# tic_tac_toe.net
KiCad netlist of a schematic drawn in EAGLE
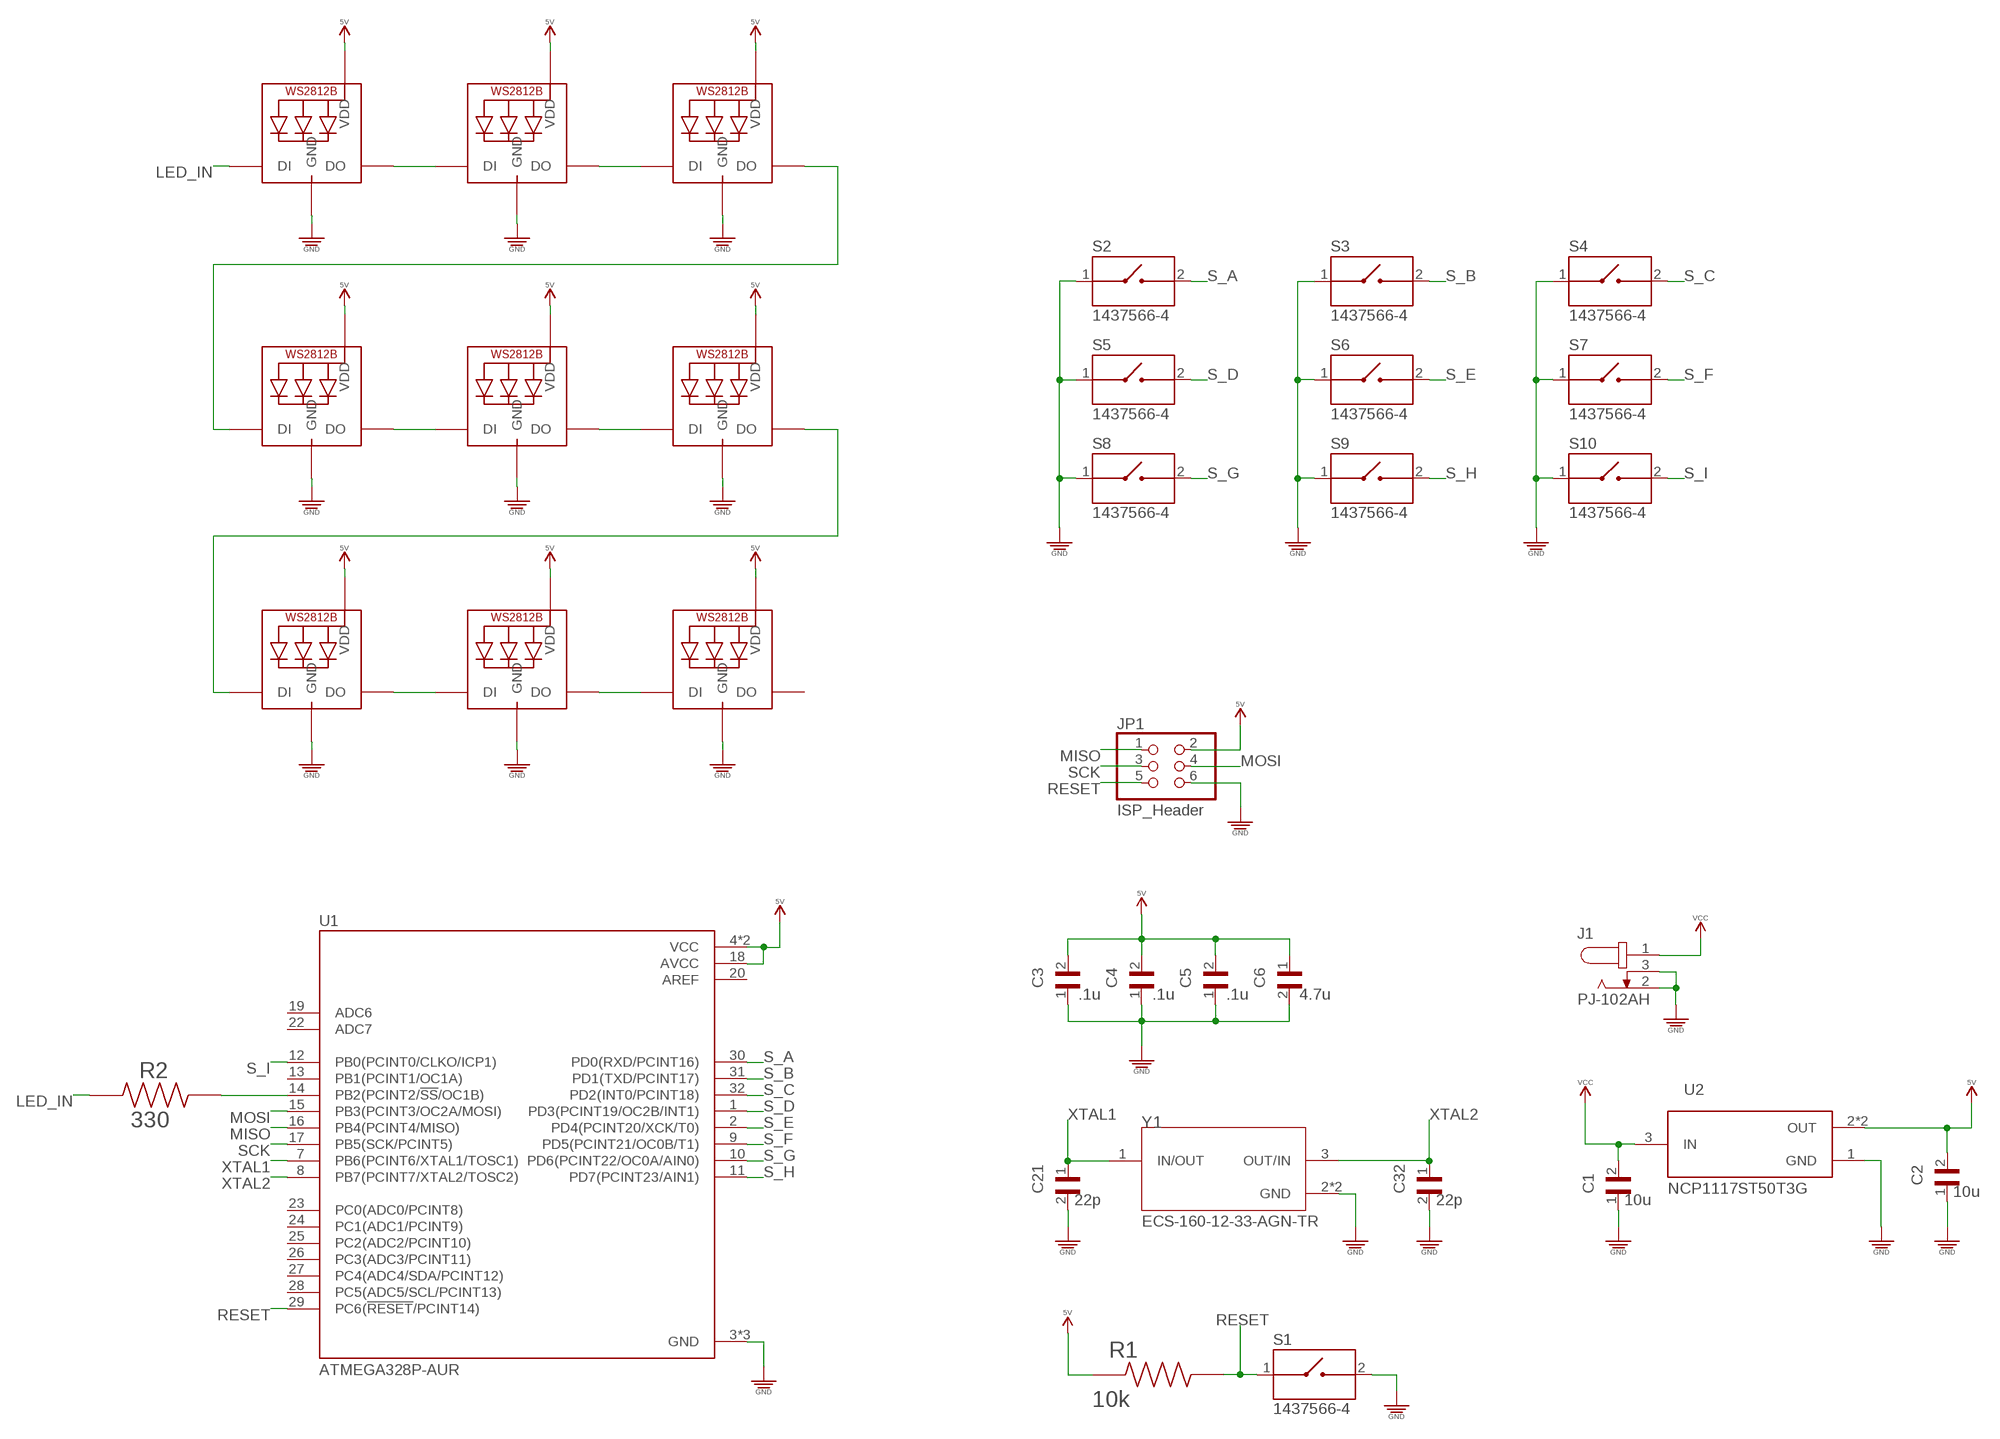
[diagram p0: schematic, sheet 1]

(export (version "E")
  (design (tool "Eeschema 10.0.6"))
  (components
    (comp (ref "C1")
      (value "10u")
      (footprint "eagle-import:CAPC2012X140N")
      (fields
        (field (name "DIGI-KEY_PART_NUMBER") "478-3051-1-ND")
        (field (name "MF") "AVX")
        (field (name "MP") "TAJR106M006R")
      )
      (libsource (lib "eagle-import") (part "TAJR106M006R"))
    )
    (comp (ref "C2")
      (value "10u")
      (footprint "eagle-import:CAPC2012X140N")
      (fields
        (field (name "DIGI-KEY_PART_NUMBER") "478-3051-1-ND")
        (field (name "MF") "AVX")
        (field (name "MP") "TAJR106M006R")
      )
      (libsource (lib "eagle-import") (part "TAJR106M006R"))
    )
    (comp (ref "C3")
      (value ".1u")
      (footprint "eagle-import:CAPC2012X140N")
      (fields
        (field (name "DIGI-KEY_PART_NUMBER") "478-3614-1-ND")
        (field (name "MF") "AVX")
        (field (name "MP") "08055F104K4T2A")
      )
      (libsource (lib "eagle-import") (part "08055F104K4T2A"))
    )
    (comp (ref "C4")
      (value ".1u")
      (footprint "eagle-import:CAPC2012X140N")
      (fields
        (field (name "DIGI-KEY_PART_NUMBER") "478-3614-1-ND")
        (field (name "MF") "AVX")
        (field (name "MP") "08055F104K4T2A")
      )
      (libsource (lib "eagle-import") (part "08055F104K4T2A"))
    )
    (comp (ref "C5")
      (value ".1u")
      (footprint "eagle-import:CAPC2012X140N")
      (fields
        (field (name "DIGI-KEY_PART_NUMBER") "478-3614-1-ND")
        (field (name "MF") "AVX")
        (field (name "MP") "08055F104K4T2A")
      )
      (libsource (lib "eagle-import") (part "08055F104K4T2A"))
    )
    (comp (ref "C6")
      (value "4.7u")
      (footprint "eagle-import:CAPC2012X140N")
      (fields
        (field (name "DIGI-KEY_PART_NUMBER") "1276-1244-1-ND")
        (field (name "MF") "Samsung Electro-Mechanics")
        (field (name "MP") "CL21A475KAQNNNE")
      )
      (libsource (lib "eagle-import") (part "CL21A475KAQNNNE"))
    )
    (comp (ref "C21")
      (value "22p")
      (footprint "eagle-import:CAPC2012X140N")
      (fields
        (field (name "DIGI-KEY_PART_NUMBER") "399-C0805C220J5GAC7800CT-ND")
        (field (name "MF") "KEMET")
        (field (name "MP") "C0805C220J5GACTU")
      )
      (libsource (lib "eagle-import") (part "C0805C220J5GACTU"))
    )
    (comp (ref "C32")
      (value "22p")
      (footprint "eagle-import:CAPC2012X140N")
      (fields
        (field (name "DIGI-KEY_PART_NUMBER") "399-C0805C220J5GAC7800CT-ND")
        (field (name "MF") "KEMET")
        (field (name "MP") "C0805C220J5GACTU")
      )
      (libsource (lib "eagle-import") (part "C0805C220J5GACTU"))
    )
    (comp (ref "J1")
      (value "PJ-102AH")
      (footprint "eagle-import:CUI_PJ-102AH")
      (fields (field (name "MF") "CUI Devices"))
      (libsource (lib "eagle-import") (part "PJ-102AH"))
    )
    (comp (ref "JP1")
      (value "ISP_Header")
      (footprint "eagle-import:2X03")
      (libsource (lib "eagle-import") (part "PINHD-2X3"))
    )
    (comp (ref "LED1")
      (value "MICROBUILDER_WS2812B_SK6812E")
      (footprint "eagle-import:MICROBUILDER_NEO3535_REVERSE")
      (libsource (lib "eagle-import") (part "MICROBUILDER_WS2812B_SK6812E"))
    )
    (comp (ref "LED2")
      (value "MICROBUILDER_WS2812B_SK6812E")
      (footprint "eagle-import:MICROBUILDER_NEO3535_REVERSE")
      (libsource (lib "eagle-import") (part "MICROBUILDER_WS2812B_SK6812E"))
    )
    (comp (ref "LED3")
      (value "MICROBUILDER_WS2812B_SK6812E")
      (footprint "eagle-import:MICROBUILDER_NEO3535_REVERSE")
      (libsource (lib "eagle-import") (part "MICROBUILDER_WS2812B_SK6812E"))
    )
    (comp (ref "LED4")
      (value "MICROBUILDER_WS2812B_SK6812E")
      (footprint "eagle-import:MICROBUILDER_NEO3535_REVERSE")
      (libsource (lib "eagle-import") (part "MICROBUILDER_WS2812B_SK6812E"))
    )
    (comp (ref "LED5")
      (value "MICROBUILDER_WS2812B_SK6812E")
      (footprint "eagle-import:MICROBUILDER_NEO3535_REVERSE")
      (libsource (lib "eagle-import") (part "MICROBUILDER_WS2812B_SK6812E"))
    )
    (comp (ref "LED6")
      (value "MICROBUILDER_WS2812B_SK6812E")
      (footprint "eagle-import:MICROBUILDER_NEO3535_REVERSE")
      (libsource (lib "eagle-import") (part "MICROBUILDER_WS2812B_SK6812E"))
    )
    (comp (ref "LED7")
      (value "MICROBUILDER_WS2812B_SK6812E")
      (footprint "eagle-import:MICROBUILDER_NEO3535_REVERSE")
      (libsource (lib "eagle-import") (part "MICROBUILDER_WS2812B_SK6812E"))
    )
    (comp (ref "LED8")
      (value "MICROBUILDER_WS2812B_SK6812E")
      (footprint "eagle-import:MICROBUILDER_NEO3535_REVERSE")
      (libsource (lib "eagle-import") (part "MICROBUILDER_WS2812B_SK6812E"))
    )
    (comp (ref "LED9")
      (value "MICROBUILDER_WS2812B_SK6812E")
      (footprint "eagle-import:MICROBUILDER_NEO3535_REVERSE")
      (libsource (lib "eagle-import") (part "MICROBUILDER_WS2812B_SK6812E"))
    )
    (comp (ref "R1")
      (value "10k")
      (footprint "eagle-import:RESC2012X60N")
      (fields
        (field (name "DIGI-KEY_PART_NUMBER") "CR0805-FX-1002ELFTR-ND")
        (field (name "MF") "Bourns")
        (field (name "MP") "CR0805-FX-1002ELF")
      )
      (libsource (lib "eagle-import") (part "CR0805-FX-1002ELF"))
    )
    (comp (ref "R2")
      (value "330")
      (footprint "eagle-import:RESC3116X65N")
      (fields
        (field (name "DIGI-KEY_PART_NUMBER") "311-330FRCT-ND")
        (field (name "MF") "Yageo")
        (field (name "MP") "RC1206FR-07330RL")
      )
      (libsource (lib "eagle-import") (part "RC1206FR-07330RL"))
    )
    (comp (ref "S1")
      (value "1437566-4")
      (footprint "eagle-import:SW_1437566-4")
      (fields
        (field (name "DIGI-KEY_PART_NUMBER") "2266-1437566-4TR-ND")
        (field (name "MF") "TE Connectivity")
      )
      (libsource (lib "eagle-import") (part "1437566-4"))
    )
    (comp (ref "S2")
      (value "1437566-4")
      (footprint "eagle-import:SW_1437566-4")
      (fields
        (field (name "DIGI-KEY_PART_NUMBER") "2266-1437566-4TR-ND")
        (field (name "MF") "TE Connectivity")
      )
      (libsource (lib "eagle-import") (part "1437566-4"))
    )
    (comp (ref "S3")
      (value "1437566-4")
      (footprint "eagle-import:SW_1437566-4")
      (fields
        (field (name "DIGI-KEY_PART_NUMBER") "2266-1437566-4TR-ND")
        (field (name "MF") "TE Connectivity")
      )
      (libsource (lib "eagle-import") (part "1437566-4"))
    )
    (comp (ref "S4")
      (value "1437566-4")
      (footprint "eagle-import:SW_1437566-4")
      (fields
        (field (name "DIGI-KEY_PART_NUMBER") "2266-1437566-4TR-ND")
        (field (name "MF") "TE Connectivity")
      )
      (libsource (lib "eagle-import") (part "1437566-4"))
    )
    (comp (ref "S5")
      (value "1437566-4")
      (footprint "eagle-import:SW_1437566-4")
      (fields
        (field (name "DIGI-KEY_PART_NUMBER") "2266-1437566-4TR-ND")
        (field (name "MF") "TE Connectivity")
      )
      (libsource (lib "eagle-import") (part "1437566-4"))
    )
    (comp (ref "S6")
      (value "1437566-4")
      (footprint "eagle-import:SW_1437566-4")
      (fields
        (field (name "DIGI-KEY_PART_NUMBER") "2266-1437566-4TR-ND")
        (field (name "MF") "TE Connectivity")
      )
      (libsource (lib "eagle-import") (part "1437566-4"))
    )
    (comp (ref "S7")
      (value "1437566-4")
      (footprint "eagle-import:SW_1437566-4")
      (fields
        (field (name "DIGI-KEY_PART_NUMBER") "2266-1437566-4TR-ND")
        (field (name "MF") "TE Connectivity")
      )
      (libsource (lib "eagle-import") (part "1437566-4"))
    )
    (comp (ref "S8")
      (value "1437566-4")
      (footprint "eagle-import:SW_1437566-4")
      (fields
        (field (name "DIGI-KEY_PART_NUMBER") "2266-1437566-4TR-ND")
        (field (name "MF") "TE Connectivity")
      )
      (libsource (lib "eagle-import") (part "1437566-4"))
    )
    (comp (ref "S9")
      (value "1437566-4")
      (footprint "eagle-import:SW_1437566-4")
      (fields
        (field (name "DIGI-KEY_PART_NUMBER") "2266-1437566-4TR-ND")
        (field (name "MF") "TE Connectivity")
      )
      (libsource (lib "eagle-import") (part "1437566-4"))
    )
    (comp (ref "S10")
      (value "1437566-4")
      (footprint "eagle-import:SW_1437566-4")
      (fields
        (field (name "DIGI-KEY_PART_NUMBER") "2266-1437566-4TR-ND")
        (field (name "MF") "TE Connectivity")
      )
      (libsource (lib "eagle-import") (part "1437566-4"))
    )
    (comp (ref "U1")
      (value "ATMEGA328P-AUR")
      (footprint "eagle-import:QFP80P900X900X120-32N")
      (fields
        (field (name "DIGI-KEY_PART_NUMBER") "ATMEGA328P-AURTR-ND")
        (field (name "MF") "Microchip Technology")
      )
      (libsource (lib "eagle-import") (part "ATMEGA328P-AUR"))
    )
    (comp (ref "U2")
      (value "NCP1117ST50T3G")
      (footprint "eagle-import:SOT230P700X180-4N")
      (fields
        (field (name "DIGI-KEY_PART_NUMBER") "NCP1117ST50T3GOSCT-ND")
        (field (name "MF") "ON Semiconductor")
      )
      (libsource (lib "eagle-import") (part "NCP1117ST50T3G"))
    )
    (comp (ref "Y1")
      (value "ECS-160-12-33-AGN-TR")
      (footprint "eagle-import:XTAL_ECS-160-12-33-AGN-TR")
      (fields (field (name "DIGI-KEY_PART_NUMBER") "XC2930CT-ND") (field (name "MF") "ECS Inc."))
      (libsource (lib "eagle-import") (part "ECS-160-12-33-AGN-TR"))
    )
  )
  (nets
    (net (code "1") (name "/AREF") (class "Default")
      (node (ref "U1") (pin "20") (pinfunction "AREF_20") (pintype "power_in"))
    )
    (net (code "2") (name "/LED_IN") (class "Default")
      (node (ref "LED1") (pin "4-DIN") (pinfunction "DI_4-DIN") (pintype "input"))
      (node (ref "R2") (pin "1") (pinfunction "1_1") (pintype "passive"))
    )
    (net (code "3") (name "/MISO") (class "Default")
      (node (ref "JP1") (pin "1") (pinfunction "1_1") (pintype "passive"))
      (node (ref "U1") (pin "16") (pinfunction "PB4(PCINT4/MISO)_16") (pintype "bidirectional"))
    )
    (net (code "4") (name "/MOSI") (class "Default")
      (node (ref "JP1") (pin "4") (pinfunction "4_4") (pintype "passive"))
      (node (ref "U1") (pin "15") (pinfunction "PB3(PCINT3/OC2A/MOSI)_15") (pintype "bidirectional"))
    )
    (net (code "5") (name "/RESET") (class "Default")
      (node (ref "JP1") (pin "5") (pinfunction "5_5") (pintype "passive"))
      (node (ref "R1") (pin "2") (pinfunction "2_2") (pintype "passive"))
      (node (ref "S1") (pin "1") (pinfunction "1_1") (pintype "passive"))
      (node (ref "U1") (pin "29") (pinfunction "PC6(~{RESET}/PCINT14)_29") (pintype "bidirectional"))
    )
    (net (code "6") (name "/SCK") (class "Default")
      (node (ref "JP1") (pin "3") (pinfunction "3_3") (pintype "passive"))
      (node (ref "U1") (pin "17") (pinfunction "PB5(SCK/PCINT5)_17") (pintype "bidirectional"))
    )
    (net (code "7") (name "/S_A") (class "Default")
      (node (ref "S2") (pin "2") (pinfunction "2_2") (pintype "passive"))
      (node (ref "U1") (pin "30") (pinfunction "PD0(RXD/PCINT16)_30") (pintype "bidirectional"))
    )
    (net (code "8") (name "/S_B") (class "Default")
      (node (ref "S3") (pin "2") (pinfunction "2_2") (pintype "passive"))
      (node (ref "U1") (pin "31") (pinfunction "PD1(TXD/PCINT17)_31") (pintype "bidirectional"))
    )
    (net (code "9") (name "/S_C") (class "Default")
      (node (ref "S4") (pin "2") (pinfunction "2_2") (pintype "passive"))
      (node (ref "U1") (pin "32") (pinfunction "PD2(INT0/PCINT18)_32") (pintype "bidirectional"))
    )
    (net (code "10") (name "/S_D") (class "Default")
      (node (ref "S5") (pin "2") (pinfunction "2_2") (pintype "passive"))
      (node (ref "U1") (pin "1") (pinfunction "PD3(PCINT19/OC2B/INT1)_1") (pintype "bidirectional"))
    )
    (net (code "11") (name "/S_E") (class "Default")
      (node (ref "S6") (pin "2") (pinfunction "2_2") (pintype "passive"))
      (node (ref "U1") (pin "2") (pinfunction "PD4(PCINT20/XCK/T0)_2") (pintype "bidirectional"))
    )
    (net (code "12") (name "/S_F") (class "Default")
      (node (ref "S7") (pin "2") (pinfunction "2_2") (pintype "passive"))
      (node (ref "U1") (pin "9") (pinfunction "PD5(PCINT21/OC0B/T1)_9") (pintype "bidirectional"))
    )
    (net (code "13") (name "/S_G") (class "Default")
      (node (ref "S8") (pin "2") (pinfunction "2_2") (pintype "passive"))
      (node (ref "U1") (pin "10") (pinfunction "PD6(PCINT22/OC0A/AIN0)_10") (pintype "bidirectional"))
    )
    (net (code "14") (name "/S_H") (class "Default")
      (node (ref "S9") (pin "2") (pinfunction "2_2") (pintype "passive"))
      (node (ref "U1") (pin "11") (pinfunction "PD7(PCINT23/AIN1)_11") (pintype "bidirectional"))
    )
    (net (code "15") (name "/S_I") (class "Default")
      (node (ref "S10") (pin "2") (pinfunction "2_2") (pintype "passive"))
      (node (ref "U1") (pin "12") (pinfunction "PB0(PCINT0/CLKO/ICP1)_12") (pintype "bidirectional"))
    )
    (net (code "16") (name "/XTAL1") (class "Default")
      (node (ref "C21") (pin "1") (pinfunction "1_1") (pintype "passive"))
      (node (ref "U1") (pin "7") (pinfunction "PB6(PCINT6/XTAL1/TOSC1)_7") (pintype "bidirectional"))
      (node (ref "Y1") (pin "1") (pinfunction "IN/OUT_1") (pintype "bidirectional"))
    )
    (net (code "17") (name "/XTAL2") (class "Default")
      (node (ref "C32") (pin "1") (pinfunction "1_1") (pintype "passive"))
      (node (ref "U1") (pin "8") (pinfunction "PB7(PCINT7/XTAL2/TOSC2)_8") (pintype "bidirectional"))
      (node (ref "Y1") (pin "3") (pinfunction "OUT/IN_3") (pintype "bidirectional"))
    )
    (net (code "18") (name "5V") (class "Default")
      (node (ref "C2") (pin "2") (pinfunction "2_2") (pintype "passive"))
      (node (ref "C3") (pin "2") (pinfunction "2_2") (pintype "passive"))
      (node (ref "C4") (pin "2") (pinfunction "2_2") (pintype "passive"))
      (node (ref "C5") (pin "2") (pinfunction "2_2") (pintype "passive"))
      (node (ref "C6") (pin "1") (pinfunction "1_1") (pintype "passive"))
      (node (ref "JP1") (pin "2") (pinfunction "2_2") (pintype "passive"))
      (node (ref "LED1") (pin "1-VDD") (pinfunction "VDD_1-VDD") (pintype "power_in"))
      (node (ref "LED2") (pin "1-VDD") (pinfunction "VDD_1-VDD") (pintype "power_in"))
      (node (ref "LED3") (pin "1-VDD") (pinfunction "VDD_1-VDD") (pintype "power_in"))
      (node (ref "LED4") (pin "1-VDD") (pinfunction "VDD_1-VDD") (pintype "power_in"))
      (node (ref "LED5") (pin "1-VDD") (pinfunction "VDD_1-VDD") (pintype "power_in"))
      (node (ref "LED6") (pin "1-VDD") (pinfunction "VDD_1-VDD") (pintype "power_in"))
      (node (ref "LED7") (pin "1-VDD") (pinfunction "VDD_1-VDD") (pintype "power_in"))
      (node (ref "LED8") (pin "1-VDD") (pinfunction "VDD_1-VDD") (pintype "power_in"))
      (node (ref "LED9") (pin "1-VDD") (pinfunction "VDD_1-VDD") (pintype "power_in"))
      (node (ref "R1") (pin "1") (pinfunction "1_1") (pintype "passive"))
      (node (ref "U1") (pin "18") (pinfunction "AVCC_18") (pintype "power_in"))
      (node (ref "U1") (pin "4") (pinfunction "VCC_4") (pintype "power_in"))
      (node (ref "U1") (pin "6") (pinfunction "VCC_6") (pintype "power_in"))
      (node (ref "U2") (pin "2") (pinfunction "OUT_2") (pintype "output"))
      (node (ref "U2") (pin "4") (pinfunction "OUT_4") (pintype "output"))
    )
    (net (code "19") (name "GND") (class "Default")
      (node (ref "C1") (pin "1") (pinfunction "1_1") (pintype "passive"))
      (node (ref "C2") (pin "1") (pinfunction "1_1") (pintype "passive"))
      (node (ref "C21") (pin "2") (pinfunction "2_2") (pintype "passive"))
      (node (ref "C3") (pin "1") (pinfunction "1_1") (pintype "passive"))
      (node (ref "C32") (pin "2") (pinfunction "2_2") (pintype "passive"))
      (node (ref "C4") (pin "1") (pinfunction "1_1") (pintype "passive"))
      (node (ref "C5") (pin "1") (pinfunction "1_1") (pintype "passive"))
      (node (ref "C6") (pin "2") (pinfunction "2_2") (pintype "passive"))
      (node (ref "J1") (pin "2") (pinfunction "2_2") (pintype "passive"))
      (node (ref "J1") (pin "3") (pinfunction "3_3") (pintype "passive"))
      (node (ref "JP1") (pin "6") (pinfunction "6_6") (pintype "passive"))
      (node (ref "LED1") (pin "3-GND") (pinfunction "GND_3-GND") (pintype "power_in"))
      (node (ref "LED2") (pin "3-GND") (pinfunction "GND_3-GND") (pintype "power_in"))
      (node (ref "LED3") (pin "3-GND") (pinfunction "GND_3-GND") (pintype "power_in"))
      (node (ref "LED4") (pin "3-GND") (pinfunction "GND_3-GND") (pintype "power_in"))
      (node (ref "LED5") (pin "3-GND") (pinfunction "GND_3-GND") (pintype "power_in"))
      (node (ref "LED6") (pin "3-GND") (pinfunction "GND_3-GND") (pintype "power_in"))
      (node (ref "LED7") (pin "3-GND") (pinfunction "GND_3-GND") (pintype "power_in"))
      (node (ref "LED8") (pin "3-GND") (pinfunction "GND_3-GND") (pintype "power_in"))
      (node (ref "LED9") (pin "3-GND") (pinfunction "GND_3-GND") (pintype "power_in"))
      (node (ref "S1") (pin "2") (pinfunction "2_2") (pintype "passive"))
      (node (ref "S10") (pin "1") (pinfunction "1_1") (pintype "passive"))
      (node (ref "S2") (pin "1") (pinfunction "1_1") (pintype "passive"))
      (node (ref "S3") (pin "1") (pinfunction "1_1") (pintype "passive"))
      (node (ref "S4") (pin "1") (pinfunction "1_1") (pintype "passive"))
      (node (ref "S5") (pin "1") (pinfunction "1_1") (pintype "passive"))
      (node (ref "S6") (pin "1") (pinfunction "1_1") (pintype "passive"))
      (node (ref "S7") (pin "1") (pinfunction "1_1") (pintype "passive"))
      (node (ref "S8") (pin "1") (pinfunction "1_1") (pintype "passive"))
      (node (ref "S9") (pin "1") (pinfunction "1_1") (pintype "passive"))
      (node (ref "U1") (pin "21") (pinfunction "GND_21") (pintype "power_in"))
      (node (ref "U1") (pin "3") (pinfunction "GND_3") (pintype "power_in"))
      (node (ref "U1") (pin "5") (pinfunction "GND_5") (pintype "power_in"))
      (node (ref "U2") (pin "1") (pinfunction "GND_1") (pintype "power_in"))
      (node (ref "Y1") (pin "2") (pinfunction "GND_2") (pintype "power_in"))
      (node (ref "Y1") (pin "4") (pinfunction "GND_4") (pintype "power_in"))
    )
    (net (code "20") (name "Net-(LED1-DO)") (class "Default")
      (node (ref "LED1") (pin "2-DOUT") (pinfunction "DO_2-DOUT") (pintype "output"))
      (node (ref "LED2") (pin "4-DIN") (pinfunction "DI_4-DIN") (pintype "input"))
    )
    (net (code "21") (name "Net-(LED2-DO)") (class "Default")
      (node (ref "LED2") (pin "2-DOUT") (pinfunction "DO_2-DOUT") (pintype "output"))
      (node (ref "LED3") (pin "4-DIN") (pinfunction "DI_4-DIN") (pintype "input"))
    )
    (net (code "22") (name "Net-(LED3-DO)") (class "Default")
      (node (ref "LED3") (pin "2-DOUT") (pinfunction "DO_2-DOUT") (pintype "output"))
      (node (ref "LED4") (pin "4-DIN") (pinfunction "DI_4-DIN") (pintype "input"))
    )
    (net (code "23") (name "Net-(LED4-DO)") (class "Default")
      (node (ref "LED4") (pin "2-DOUT") (pinfunction "DO_2-DOUT") (pintype "output"))
      (node (ref "LED5") (pin "4-DIN") (pinfunction "DI_4-DIN") (pintype "input"))
    )
    (net (code "24") (name "Net-(LED5-DO)") (class "Default")
      (node (ref "LED5") (pin "2-DOUT") (pinfunction "DO_2-DOUT") (pintype "output"))
      (node (ref "LED6") (pin "4-DIN") (pinfunction "DI_4-DIN") (pintype "input"))
    )
    (net (code "25") (name "Net-(LED6-DO)") (class "Default")
      (node (ref "LED6") (pin "2-DOUT") (pinfunction "DO_2-DOUT") (pintype "output"))
      (node (ref "LED7") (pin "4-DIN") (pinfunction "DI_4-DIN") (pintype "input"))
    )
    (net (code "26") (name "Net-(LED7-DO)") (class "Default")
      (node (ref "LED7") (pin "2-DOUT") (pinfunction "DO_2-DOUT") (pintype "output"))
      (node (ref "LED8") (pin "4-DIN") (pinfunction "DI_4-DIN") (pintype "input"))
    )
    (net (code "27") (name "Net-(LED8-DO)") (class "Default")
      (node (ref "LED8") (pin "2-DOUT") (pinfunction "DO_2-DOUT") (pintype "output"))
      (node (ref "LED9") (pin "4-DIN") (pinfunction "DI_4-DIN") (pintype "input"))
    )
    (net (code "28") (name "Net-(U1-PB2(PCINT2{slash}~{SS}{slash}OC1B))") (class "Default")
      (node (ref "R2") (pin "2") (pinfunction "2_2") (pintype "passive"))
      (node (ref "U1") (pin "14") (pinfunction "PB2(PCINT2/~{SS}/OC1B)_14") (pintype "bidirectional"))
    )
    (net (code "29") (name "VCC") (class "Default")
      (node (ref "C1") (pin "2") (pinfunction "2_2") (pintype "passive"))
      (node (ref "J1") (pin "1") (pinfunction "1_1") (pintype "passive"))
      (node (ref "U2") (pin "3") (pinfunction "IN_3") (pintype "input"))
    )
    (net (code "30") (name "unconnected-(LED9-DO-Pad2-DOUT)") (class "Default")
      (node (ref "LED9") (pin "2-DOUT") (pinfunction "DO_2-DOUT") (pintype "output"))
    )
    (net (code "31") (name "unconnected-(U1-ADC6-Pad19)") (class "Default")
      (node (ref "U1") (pin "19") (pinfunction "ADC6_19") (pintype "input"))
    )
    (net (code "32") (name "unconnected-(U1-ADC7-Pad22)") (class "Default")
      (node (ref "U1") (pin "22") (pinfunction "ADC7_22") (pintype "input"))
    )
    (net (code "33") (name "unconnected-(U1-PB1(PCINT1{slash}OC1A)-Pad13)") (class "Default")
      (node (ref "U1") (pin "13") (pinfunction "PB1(PCINT1/OC1A)_13") (pintype "bidirectional"))
    )
    (net (code "34") (name "unconnected-(U1-PC0(ADC0{slash}PCINT8)-Pad23)") (class "Default")
      (node (ref "U1") (pin "23") (pinfunction "PC0(ADC0/PCINT8)_23") (pintype "bidirectional"))
    )
    (net (code "35") (name "unconnected-(U1-PC1(ADC1{slash}PCINT9)-Pad24)") (class "Default")
      (node (ref "U1") (pin "24") (pinfunction "PC1(ADC1/PCINT9)_24") (pintype "bidirectional"))
    )
    (net (code "36") (name "unconnected-(U1-PC2(ADC2{slash}PCINT10)-Pad25)") (class "Default")
      (node (ref "U1") (pin "25") (pinfunction "PC2(ADC2/PCINT10)_25") (pintype "bidirectional"))
    )
    (net (code "37") (name "unconnected-(U1-PC3(ADC3{slash}PCINT11)-Pad26)") (class "Default")
      (node (ref "U1") (pin "26") (pinfunction "PC3(ADC3/PCINT11)_26") (pintype "bidirectional"))
    )
    (net (code "38") (name "unconnected-(U1-PC4(ADC4{slash}SDA{slash}PCINT12)-Pad27)") (class "Default")
      (node (ref "U1") (pin "27") (pinfunction "PC4(ADC4/SDA/PCINT12)_27") (pintype "bidirectional"))
    )
    (net (code "39") (name "unconnected-(U1-PC5(ADC5{slash}SCL{slash}PCINT13)-Pad28)") (class "Default")
      (node (ref "U1") (pin "28") (pinfunction "PC5(ADC5/SCL/PCINT13)_28") (pintype "bidirectional"))
    )
  )
)
